# smartHome.net
KiCad netlist of a schematic drawn in EAGLE
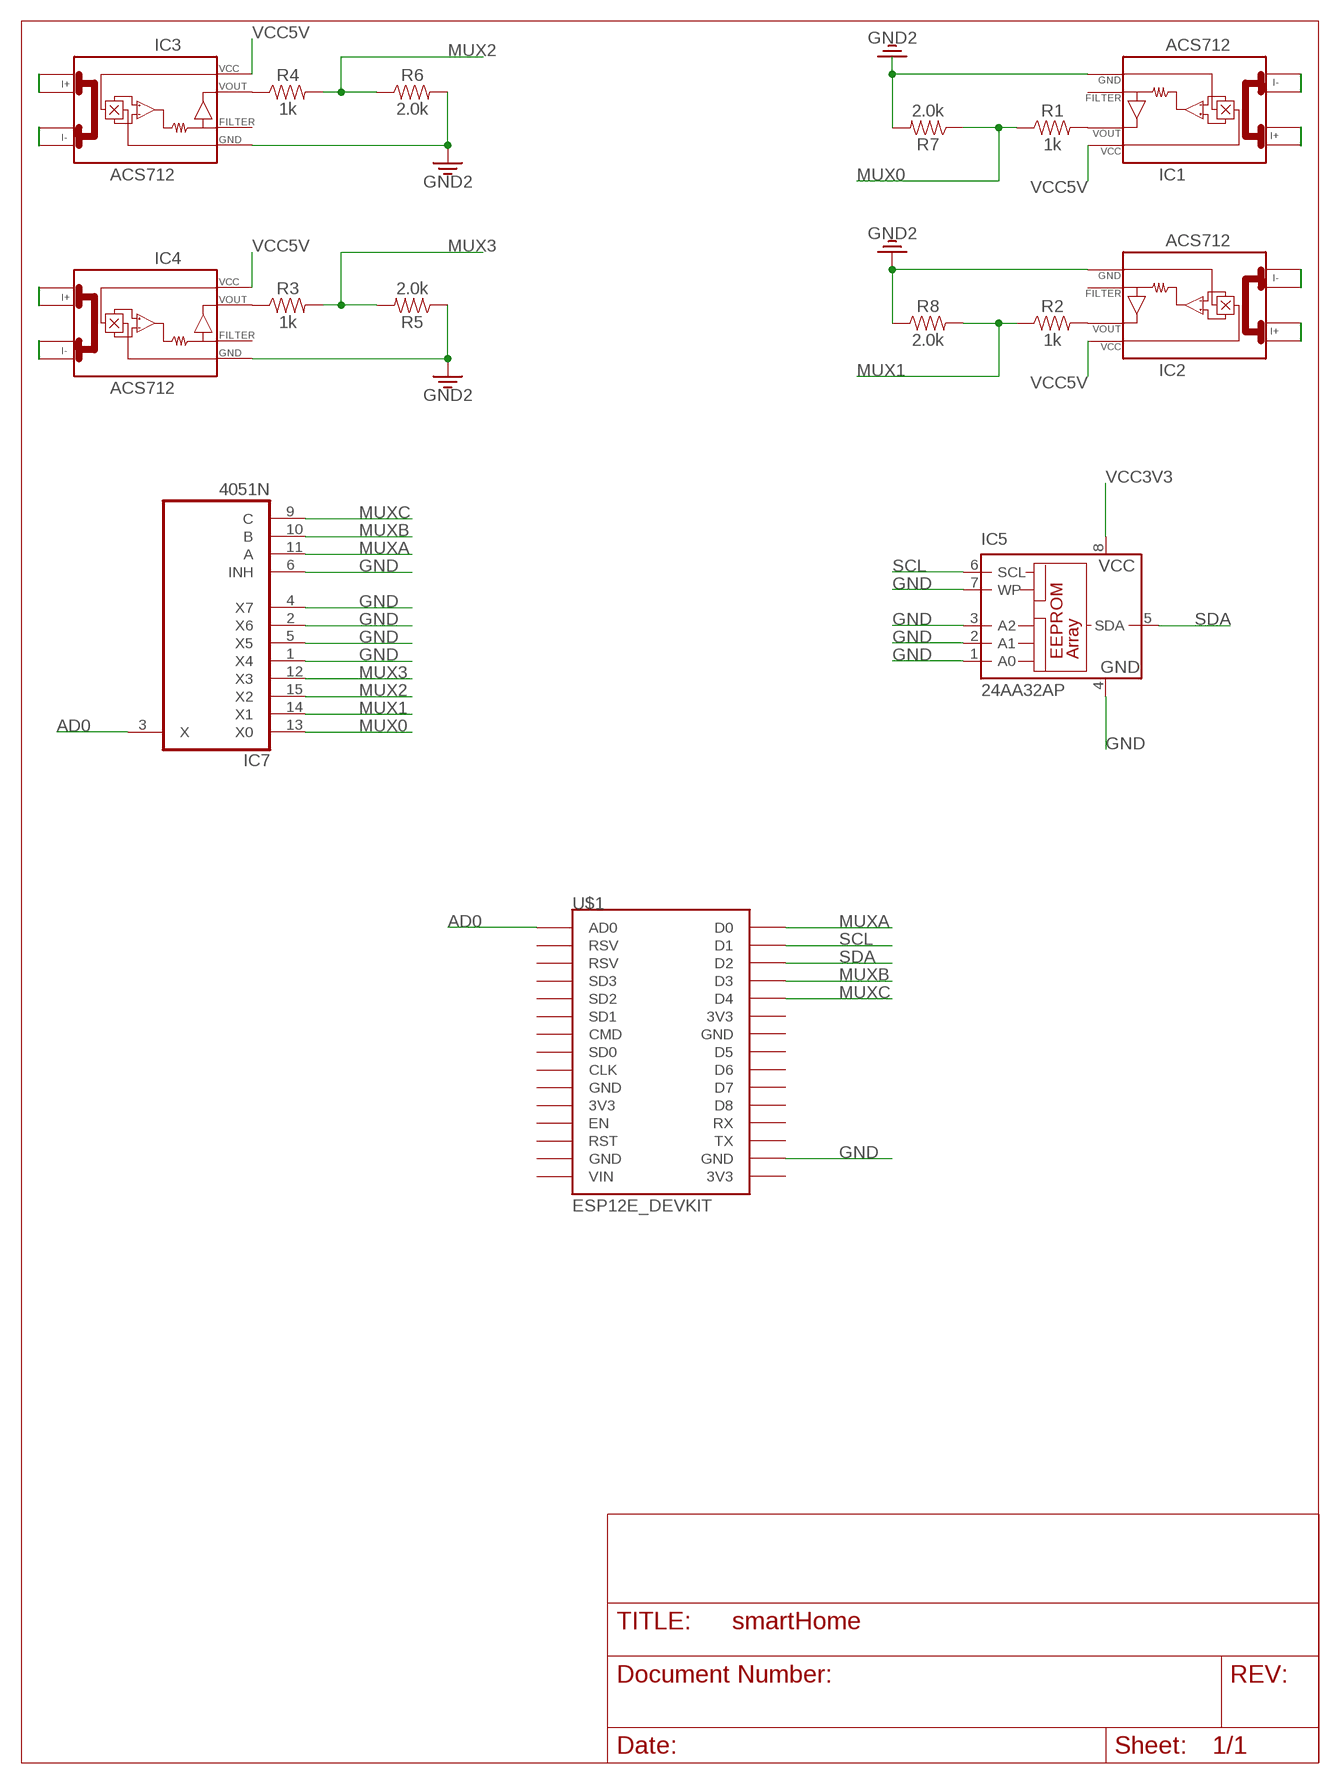
[diagram p0: schematic, sheet 1]

(export (version "E")
  (design (tool "Eeschema 10.0.6"))
  (components
    (comp (ref "IC1")
      (value "ACS712")
      (footprint "eagle-import:SO08")
      (libsource (lib "eagle-import") (part "ACS712"))
    )
    (comp (ref "IC2")
      (value "ACS712")
      (footprint "eagle-import:SO08")
      (libsource (lib "eagle-import") (part "ACS712"))
    )
    (comp (ref "IC3")
      (value "ACS712")
      (footprint "eagle-import:SO08")
      (libsource (lib "eagle-import") (part "ACS712"))
    )
    (comp (ref "IC4")
      (value "ACS712")
      (footprint "eagle-import:SO08")
      (libsource (lib "eagle-import") (part "ACS712"))
    )
    (comp (ref "IC5")
      (value "24AA32AP")
      (footprint "eagle-import:DIL8")
      (fields (field (name "MF") "MICROCHIP") (field (name "MPN") "24AA32A-I/P"))
      (libsource (lib "eagle-import") (part "24PAA32A"))
    )
    (comp (ref "IC7")
      (value "4051N")
      (footprint "eagle-import:DIL16")
      (libsource (lib "eagle-import") (part "4051N"))
    )
    (comp (ref "R1")
      (value "1k")
      (footprint "eagle-import:AXIAL-0.3")
      (libsource (lib "eagle-import") (part "1KOHM-HORIZ-1/4W-1%"))
    )
    (comp (ref "R2")
      (value "1k")
      (footprint "eagle-import:AXIAL-0.3")
      (libsource (lib "eagle-import") (part "1KOHM-HORIZ-1/4W-1%"))
    )
    (comp (ref "R3")
      (value "1k")
      (footprint "eagle-import:AXIAL-0.3")
      (libsource (lib "eagle-import") (part "1KOHM-HORIZ-1/4W-1%"))
    )
    (comp (ref "R4")
      (value "1k")
      (footprint "eagle-import:AXIAL-0.3")
      (libsource (lib "eagle-import") (part "1KOHM-HORIZ-1/4W-1%"))
    )
    (comp (ref "R5")
      (value "2.0k")
      (footprint "eagle-import:0603")
      (libsource (lib "eagle-import") (part "2.0KOHM-0603-1/10W-5%"))
    )
    (comp (ref "R6")
      (value "2.0k")
      (footprint "eagle-import:0603")
      (libsource (lib "eagle-import") (part "2.0KOHM-0603-1/10W-5%"))
    )
    (comp (ref "R7")
      (value "2.0k")
      (footprint "eagle-import:0603")
      (libsource (lib "eagle-import") (part "2.0KOHM-0603-1/10W-5%"))
    )
    (comp (ref "R8")
      (value "2.0k")
      (footprint "eagle-import:0603")
      (libsource (lib "eagle-import") (part "2.0KOHM-0603-1/10W-5%"))
    )
    (comp (ref "U$1")
      (value "ESP12E_DEVKIT")
      (footprint "eagle-import:ESP12E_DEVKIT")
      (libsource (lib "eagle-import") (part "ESP12E_DEVKIT"))
    )
  )
  (nets
    (net (code "1") (name "/AD0") (class "Default")
      (node (ref "IC7") (pin "3") (pinfunction "X_3") (pintype "bidirectional"))
      (node (ref "U$1") (pin "AD0") (pinfunction "AD0_AD0") (pintype "bidirectional"))
    )
    (net (code "2") (name "/MUX0") (class "Default")
      (node (ref "IC7") (pin "13") (pinfunction "X0_13") (pintype "bidirectional"))
      (node (ref "R1") (pin "P$1") (pinfunction "1_P$1") (pintype "passive"))
      (node (ref "R7") (pin "1") (pinfunction "1_1") (pintype "passive"))
    )
    (net (code "3") (name "/MUX1") (class "Default")
      (node (ref "IC7") (pin "14") (pinfunction "X1_14") (pintype "bidirectional"))
      (node (ref "R2") (pin "P$1") (pinfunction "1_P$1") (pintype "passive"))
      (node (ref "R8") (pin "2") (pinfunction "2_2") (pintype "passive"))
    )
    (net (code "4") (name "/MUX2") (class "Default")
      (node (ref "IC7") (pin "15") (pinfunction "X2_15") (pintype "bidirectional"))
      (node (ref "R4") (pin "P$2") (pinfunction "2_P$2") (pintype "passive"))
      (node (ref "R6") (pin "1") (pinfunction "1_1") (pintype "passive"))
    )
    (net (code "5") (name "/MUX3") (class "Default")
      (node (ref "IC7") (pin "12") (pinfunction "X3_12") (pintype "bidirectional"))
      (node (ref "R3") (pin "P$2") (pinfunction "2_P$2") (pintype "passive"))
      (node (ref "R5") (pin "2") (pinfunction "2_2") (pintype "passive"))
    )
    (net (code "6") (name "/MUXA") (class "Default")
      (node (ref "IC7") (pin "11") (pinfunction "A_11") (pintype "input"))
      (node (ref "U$1") (pin "D0") (pinfunction "D0_D0") (pintype "bidirectional"))
    )
    (net (code "7") (name "/MUXB") (class "Default")
      (node (ref "IC7") (pin "10") (pinfunction "B_10") (pintype "input"))
      (node (ref "U$1") (pin "D3") (pinfunction "D3_D3") (pintype "bidirectional"))
    )
    (net (code "8") (name "/MUXC") (class "Default")
      (node (ref "IC7") (pin "9") (pinfunction "C_9") (pintype "input"))
      (node (ref "U$1") (pin "D4") (pinfunction "D4_D4") (pintype "bidirectional"))
    )
    (net (code "9") (name "/SCL") (class "Default")
      (node (ref "IC5") (pin "6") (pinfunction "SCL_6") (pintype "input"))
      (node (ref "U$1") (pin "D1") (pinfunction "D1_D1") (pintype "bidirectional"))
    )
    (net (code "10") (name "/SDA") (class "Default")
      (node (ref "IC5") (pin "5") (pinfunction "SDA_5") (pintype "bidirectional"))
      (node (ref "U$1") (pin "D2") (pinfunction "D2_D2") (pintype "bidirectional"))
    )
    (net (code "11") (name "/VCC3V3") (class "Default")
      (node (ref "IC5") (pin "8") (pinfunction "VCC_8") (pintype "power_in"))
    )
    (net (code "12") (name "/VCC5V") (class "Default")
      (node (ref "IC1") (pin "8") (pinfunction "VCC_8") (pintype "power_in"))
      (node (ref "IC2") (pin "8") (pinfunction "VCC_8") (pintype "power_in"))
      (node (ref "IC3") (pin "8") (pinfunction "VCC_8") (pintype "power_in"))
      (node (ref "IC4") (pin "8") (pinfunction "VCC_8") (pintype "power_in"))
    )
    (net (code "13") (name "GND2") (class "Default")
      (node (ref "IC1") (pin "5") (pinfunction "GND_5") (pintype "power_in"))
      (node (ref "IC2") (pin "5") (pinfunction "GND_5") (pintype "power_in"))
      (node (ref "IC3") (pin "5") (pinfunction "GND_5") (pintype "power_in"))
      (node (ref "IC4") (pin "5") (pinfunction "GND_5") (pintype "power_in"))
      (node (ref "IC5") (pin "1") (pinfunction "A0_1") (pintype "input"))
      (node (ref "IC5") (pin "2") (pinfunction "A1_2") (pintype "input"))
      (node (ref "IC5") (pin "3") (pinfunction "A2_3") (pintype "input"))
      (node (ref "IC5") (pin "4") (pinfunction "GND_4") (pintype "power_in"))
      (node (ref "IC5") (pin "7") (pinfunction "WP_7") (pintype "input"))
      (node (ref "IC7") (pin "1") (pinfunction "X4_1") (pintype "bidirectional"))
      (node (ref "IC7") (pin "2") (pinfunction "X6_2") (pintype "bidirectional"))
      (node (ref "IC7") (pin "4") (pinfunction "X7_4") (pintype "bidirectional"))
      (node (ref "IC7") (pin "5") (pinfunction "X5_5") (pintype "bidirectional"))
      (node (ref "IC7") (pin "6") (pinfunction "INH_6") (pintype "input"))
      (node (ref "R5") (pin "1") (pinfunction "1_1") (pintype "passive"))
      (node (ref "R6") (pin "2") (pinfunction "2_2") (pintype "passive"))
      (node (ref "R7") (pin "2") (pinfunction "2_2") (pintype "passive"))
      (node (ref "R8") (pin "1") (pinfunction "1_1") (pintype "passive"))
      (node (ref "U$1") (pin "GND@3") (pinfunction "GND_GND@3") (pintype "bidirectional"))
    )
    (net (code "14") (name "Net-(IC1-VOUT)") (class "Default")
      (node (ref "IC1") (pin "7") (pinfunction "VOUT_7") (pintype "output"))
      (node (ref "R1") (pin "P$2") (pinfunction "2_P$2") (pintype "passive"))
    )
    (net (code "15") (name "Net-(IC2-VOUT)") (class "Default")
      (node (ref "IC2") (pin "7") (pinfunction "VOUT_7") (pintype "output"))
      (node (ref "R2") (pin "P$2") (pinfunction "2_P$2") (pintype "passive"))
    )
    (net (code "16") (name "Net-(IC3-VOUT)") (class "Default")
      (node (ref "IC3") (pin "7") (pinfunction "VOUT_7") (pintype "output"))
      (node (ref "R4") (pin "P$1") (pinfunction "1_P$1") (pintype "passive"))
    )
    (net (code "17") (name "Net-(IC4-VOUT)") (class "Default")
      (node (ref "IC4") (pin "7") (pinfunction "VOUT_7") (pintype "output"))
      (node (ref "R3") (pin "P$1") (pinfunction "1_P$1") (pintype "passive"))
    )
    (net (code "18") (name "unconnected-(IC1-FILTER-Pad6)") (class "Default")
      (node (ref "IC1") (pin "6") (pinfunction "FILTER_6") (pintype "bidirectional"))
    )
    (net (code "19") (name "unconnected-(IC1-I+_0-Pad1)") (class "Default")
      (node (ref "IC1") (pin "1") (pinfunction "I+_0_1") (pintype "bidirectional"))
    )
    (net (code "20") (name "unconnected-(IC1-I+_1-Pad2)") (class "Default")
      (node (ref "IC1") (pin "2") (pinfunction "I+_1_2") (pintype "bidirectional"))
    )
    (net (code "21") (name "unconnected-(IC1-I-_0-Pad3)") (class "Default")
      (node (ref "IC1") (pin "3") (pinfunction "I-_0_3") (pintype "bidirectional"))
    )
    (net (code "22") (name "unconnected-(IC1-I-_1-Pad4)") (class "Default")
      (node (ref "IC1") (pin "4") (pinfunction "I-_1_4") (pintype "bidirectional"))
    )
    (net (code "23") (name "unconnected-(IC2-FILTER-Pad6)") (class "Default")
      (node (ref "IC2") (pin "6") (pinfunction "FILTER_6") (pintype "bidirectional"))
    )
    (net (code "24") (name "unconnected-(IC2-I+_0-Pad1)") (class "Default")
      (node (ref "IC2") (pin "1") (pinfunction "I+_0_1") (pintype "bidirectional"))
    )
    (net (code "25") (name "unconnected-(IC2-I+_1-Pad2)") (class "Default")
      (node (ref "IC2") (pin "2") (pinfunction "I+_1_2") (pintype "bidirectional"))
    )
    (net (code "26") (name "unconnected-(IC2-I-_0-Pad3)") (class "Default")
      (node (ref "IC2") (pin "3") (pinfunction "I-_0_3") (pintype "bidirectional"))
    )
    (net (code "27") (name "unconnected-(IC2-I-_1-Pad4)") (class "Default")
      (node (ref "IC2") (pin "4") (pinfunction "I-_1_4") (pintype "bidirectional"))
    )
    (net (code "28") (name "unconnected-(IC3-FILTER-Pad6)") (class "Default")
      (node (ref "IC3") (pin "6") (pinfunction "FILTER_6") (pintype "bidirectional"))
    )
    (net (code "29") (name "unconnected-(IC3-I+_0-Pad1)") (class "Default")
      (node (ref "IC3") (pin "1") (pinfunction "I+_0_1") (pintype "bidirectional"))
    )
    (net (code "30") (name "unconnected-(IC3-I+_1-Pad2)") (class "Default")
      (node (ref "IC3") (pin "2") (pinfunction "I+_1_2") (pintype "bidirectional"))
    )
    (net (code "31") (name "unconnected-(IC3-I-_0-Pad3)") (class "Default")
      (node (ref "IC3") (pin "3") (pinfunction "I-_0_3") (pintype "bidirectional"))
    )
    (net (code "32") (name "unconnected-(IC3-I-_1-Pad4)") (class "Default")
      (node (ref "IC3") (pin "4") (pinfunction "I-_1_4") (pintype "bidirectional"))
    )
    (net (code "33") (name "unconnected-(IC4-FILTER-Pad6)") (class "Default")
      (node (ref "IC4") (pin "6") (pinfunction "FILTER_6") (pintype "bidirectional"))
    )
    (net (code "34") (name "unconnected-(IC4-I+_0-Pad1)") (class "Default")
      (node (ref "IC4") (pin "1") (pinfunction "I+_0_1") (pintype "bidirectional"))
    )
    (net (code "35") (name "unconnected-(IC4-I+_1-Pad2)") (class "Default")
      (node (ref "IC4") (pin "2") (pinfunction "I+_1_2") (pintype "bidirectional"))
    )
    (net (code "36") (name "unconnected-(IC4-I-_0-Pad3)") (class "Default")
      (node (ref "IC4") (pin "3") (pinfunction "I-_0_3") (pintype "bidirectional"))
    )
    (net (code "37") (name "unconnected-(IC4-I-_1-Pad4)") (class "Default")
      (node (ref "IC4") (pin "4") (pinfunction "I-_1_4") (pintype "bidirectional"))
    )
    (net (code "38") (name "unconnected-(U$1-3V3-Pad3V3@0)") (class "Default")
      (node (ref "U$1") (pin "3V3@0") (pinfunction "3V3_3V3@0") (pintype "bidirectional"))
    )
    (net (code "39") (name "unconnected-(U$1-3V3-Pad3V3@1)") (class "Default")
      (node (ref "U$1") (pin "3V3@1") (pinfunction "3V3_3V3@1") (pintype "bidirectional"))
    )
    (net (code "40") (name "unconnected-(U$1-3V3-Pad3V3@2)") (class "Default")
      (node (ref "U$1") (pin "3V3@2") (pinfunction "3V3_3V3@2") (pintype "bidirectional"))
    )
    (net (code "41") (name "unconnected-(U$1-GND-PadGND@0)") (class "Default")
      (node (ref "U$1") (pin "GND@0") (pinfunction "GND_GND@0") (pintype "bidirectional"))
    )
    (net (code "42") (name "unconnected-(U$1-GND-PadGND@1)") (class "Default")
      (node (ref "U$1") (pin "GND@1") (pinfunction "GND_GND@1") (pintype "bidirectional"))
    )
    (net (code "43") (name "unconnected-(U$1-GND-PadGND@2)") (class "Default")
      (node (ref "U$1") (pin "GND@2") (pinfunction "GND_GND@2") (pintype "bidirectional"))
    )
    (net (code "44") (name "unconnected-(U$1-PadCLK)") (class "Default")
      (node (ref "U$1") (pin "CLK") (pinfunction "CLK_CLK") (pintype "bidirectional"))
    )
    (net (code "45") (name "unconnected-(U$1-PadCMD)") (class "Default")
      (node (ref "U$1") (pin "CMD") (pinfunction "CMD_CMD") (pintype "bidirectional"))
    )
    (net (code "46") (name "unconnected-(U$1-PadD5)") (class "Default")
      (node (ref "U$1") (pin "D5") (pinfunction "D5_D5") (pintype "bidirectional"))
    )
    (net (code "47") (name "unconnected-(U$1-PadD6)") (class "Default")
      (node (ref "U$1") (pin "D6") (pinfunction "D6_D6") (pintype "bidirectional"))
    )
    (net (code "48") (name "unconnected-(U$1-PadD7)") (class "Default")
      (node (ref "U$1") (pin "D7") (pinfunction "D7_D7") (pintype "bidirectional"))
    )
    (net (code "49") (name "unconnected-(U$1-PadD8)") (class "Default")
      (node (ref "U$1") (pin "D8") (pinfunction "D8_D8") (pintype "bidirectional"))
    )
    (net (code "50") (name "unconnected-(U$1-PadEN)") (class "Default")
      (node (ref "U$1") (pin "EN") (pinfunction "EN_EN") (pintype "bidirectional"))
    )
    (net (code "51") (name "unconnected-(U$1-PadRST)") (class "Default")
      (node (ref "U$1") (pin "RST") (pinfunction "RST_RST") (pintype "bidirectional"))
    )
    (net (code "52") (name "unconnected-(U$1-PadRX)") (class "Default")
      (node (ref "U$1") (pin "RX") (pinfunction "RX_RX") (pintype "bidirectional"))
    )
    (net (code "53") (name "unconnected-(U$1-PadSD0)") (class "Default")
      (node (ref "U$1") (pin "SD0") (pinfunction "SD0_SD0") (pintype "bidirectional"))
    )
    (net (code "54") (name "unconnected-(U$1-PadSD1)") (class "Default")
      (node (ref "U$1") (pin "SD1") (pinfunction "SD1_SD1") (pintype "bidirectional"))
    )
    (net (code "55") (name "unconnected-(U$1-PadSD2)") (class "Default")
      (node (ref "U$1") (pin "SD2") (pinfunction "SD2_SD2") (pintype "bidirectional"))
    )
    (net (code "56") (name "unconnected-(U$1-PadSD3)") (class "Default")
      (node (ref "U$1") (pin "SD3") (pinfunction "SD3_SD3") (pintype "bidirectional"))
    )
    (net (code "57") (name "unconnected-(U$1-PadTX)") (class "Default")
      (node (ref "U$1") (pin "TX") (pinfunction "TX_TX") (pintype "bidirectional"))
    )
    (net (code "58") (name "unconnected-(U$1-PadVIN)") (class "Default")
      (node (ref "U$1") (pin "VIN") (pinfunction "VIN_VIN") (pintype "bidirectional"))
    )
    (net (code "59") (name "unconnected-(U$1-RSV-PadRSV@0)") (class "Default")
      (node (ref "U$1") (pin "RSV@0") (pinfunction "RSV_RSV@0") (pintype "bidirectional"))
    )
    (net (code "60") (name "unconnected-(U$1-RSV-PadRSV@1)") (class "Default")
      (node (ref "U$1") (pin "RSV@1") (pinfunction "RSV_RSV@1") (pintype "bidirectional"))
    )
  )
)
